# SRV-1_Expansion_Board.net
KiCad netlist of a schematic drawn in EAGLE
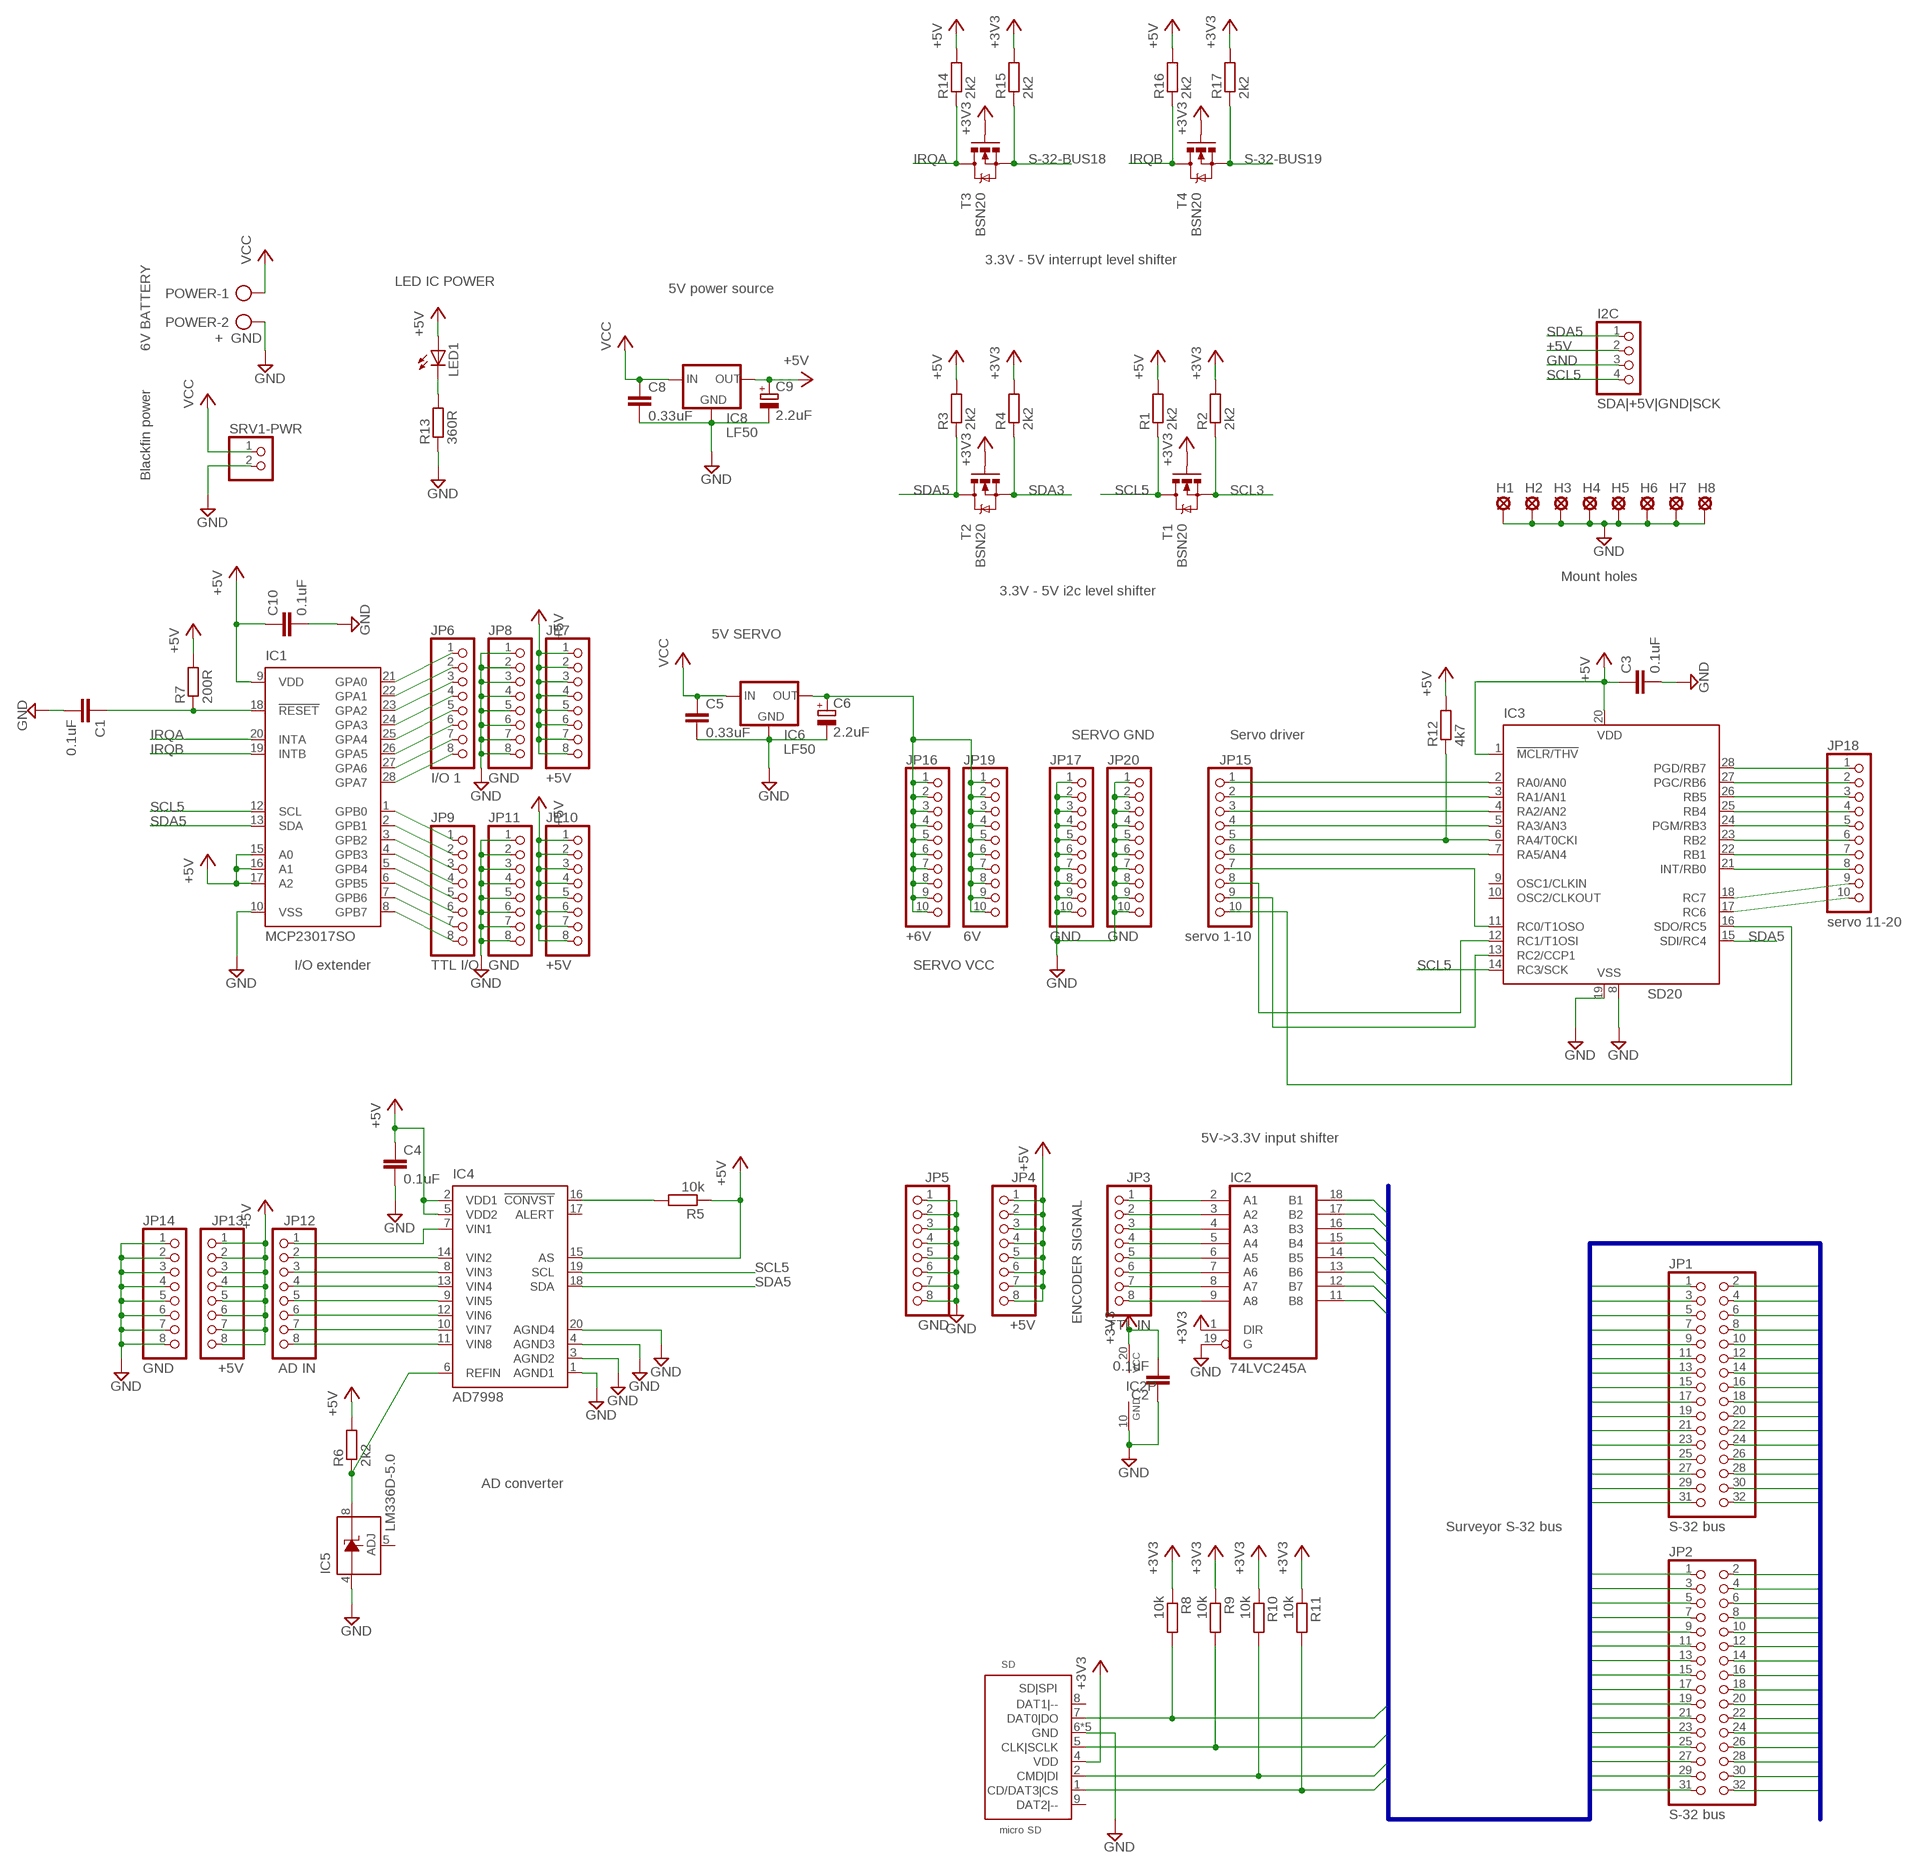
[diagram p0: schematic, sheet 1]

(export (version "E")
  (design (tool "Eeschema 10.0.6"))
  (components
    (comp (ref "C1")
      (value "0.1uF")
      (footprint "eagle-import:0805BIG")
      (libsource (lib "eagle-import") (part "CAPACITORC-0805BIG"))
    )
    (comp (ref "C2")
      (value "0.1uF")
      (footprint "eagle-import:0805BIG")
      (libsource (lib "eagle-import") (part "CAPACITORC-0805BIG"))
    )
    (comp (ref "C3")
      (value "0.1uF")
      (footprint "eagle-import:0805BIG")
      (libsource (lib "eagle-import") (part "CAPACITORC-0805BIG"))
    )
    (comp (ref "C4")
      (value "0.1uF")
      (footprint "eagle-import:0805BIG")
      (libsource (lib "eagle-import") (part "CAPACITORC-0805BIG"))
    )
    (comp (ref "C5")
      (value "0.33uF")
      (footprint "eagle-import:0805BIG")
      (libsource (lib "eagle-import") (part "CAPACITORC-0805BIG"))
    )
    (comp (ref "C6")
      (value "2.2uF")
      (footprint "eagle-import:E1,8-4")
      (libsource (lib "eagle-import") (part "CPOL-EUE1.8-4"))
    )
    (comp (ref "C8")
      (value "0.33uF")
      (footprint "eagle-import:0805BIG")
      (libsource (lib "eagle-import") (part "CAPACITORC-0805BIG"))
    )
    (comp (ref "C9")
      (value "2.2uF")
      (footprint "eagle-import:E1,8-4")
      (libsource (lib "eagle-import") (part "CPOL-EUE1.8-4"))
    )
    (comp (ref "C10")
      (value "0.1uF")
      (footprint "eagle-import:0805BIG")
      (libsource (lib "eagle-import") (part "CAPACITORC-0805BIG"))
    )
    (comp (ref "H1")
      (value "LSP35")
      (footprint "eagle-import:LSP35")
      (libsource (lib "eagle-import") (part "LSP35"))
    )
    (comp (ref "H2")
      (value "LSP35")
      (footprint "eagle-import:LSP35")
      (libsource (lib "eagle-import") (part "LSP35"))
    )
    (comp (ref "H3")
      (value "LSP35")
      (footprint "eagle-import:LSP35")
      (libsource (lib "eagle-import") (part "LSP35"))
    )
    (comp (ref "H4")
      (value "LSP35")
      (footprint "eagle-import:LSP35")
      (libsource (lib "eagle-import") (part "LSP35"))
    )
    (comp (ref "H5")
      (value "LSP40")
      (footprint "eagle-import:LSP40")
      (libsource (lib "eagle-import") (part "LSP40"))
    )
    (comp (ref "H6")
      (value "LSP40")
      (footprint "eagle-import:LSP40")
      (libsource (lib "eagle-import") (part "LSP40"))
    )
    (comp (ref "H7")
      (value "LSP40")
      (footprint "eagle-import:LSP40")
      (libsource (lib "eagle-import") (part "LSP40"))
    )
    (comp (ref "H8")
      (value "LSP40")
      (footprint "eagle-import:LSP40")
      (libsource (lib "eagle-import") (part "LSP40"))
    )
    (comp (ref "I2C")
      (value "SDA|+5V|GND|SCK")
      (footprint "eagle-import:1X04")
      (libsource (lib "eagle-import") (part "PINHD-1X4"))
    )
    (comp (ref "IC1")
      (value "MCP23017SO")
      (footprint "eagle-import:SO28W")
      (fields (field (name "MF") "MICROCHIP") (field (name "MPN") "MCP23017-E/SO"))
      (libsource (lib "eagle-import") (part "MCP23017SO"))
    )
    (comp (ref "IC2")
      (value "74LVC245A")
      (footprint "eagle-import:SO20W")
      (libsource (lib "eagle-import") (part "74245DWLS"))
    )
    (comp (ref "IC3")
      (value "SD20")
      (footprint "eagle-import:DIL28-3")
      (fields (field (name "MF") "MICROCHIP") (field (name "MPN") "PIC16F872-I/SP"))
      (libsource (lib "eagle-import") (part "PIC16872PF"))
    )
    (comp (ref "IC4")
      (value "AD7998")
      (footprint "eagle-import:TSSOP20")
      (libsource (lib "eagle-import") (part "AD7998"))
    )
    (comp (ref "IC5")
      (value "LM336D-5.0")
      (footprint "eagle-import:SO08")
      (libsource (lib "eagle-import") (part "LM336D"))
    )
    (comp (ref "IC6")
      (value "LF50")
      (footprint "eagle-import:DPAK")
      (libsource (lib "eagle-import") (part "78XXCDT"))
    )
    (comp (ref "IC8")
      (value "LF50")
      (footprint "eagle-import:DPAK")
      (libsource (lib "eagle-import") (part "78XXCDT"))
    )
    (comp (ref "JP1")
      (value "S-32 bus")
      (footprint "eagle-import:2X16")
      (libsource (lib "eagle-import") (part "PINHD-2X16"))
    )
    (comp (ref "JP2")
      (value "S-32 bus")
      (footprint "eagle-import:2X16")
      (libsource (lib "eagle-import") (part "PINHD-2X16"))
    )
    (comp (ref "JP3")
      (value "TTL IN")
      (footprint "eagle-import:1X08")
      (libsource (lib "eagle-import") (part "PINHD-1X8"))
    )
    (comp (ref "JP4")
      (value "+5V")
      (footprint "eagle-import:1X08")
      (libsource (lib "eagle-import") (part "PINHD-1X8"))
    )
    (comp (ref "JP5")
      (value "GND")
      (footprint "eagle-import:1X08")
      (libsource (lib "eagle-import") (part "PINHD-1X8"))
    )
    (comp (ref "JP6")
      (value "I/O 1")
      (footprint "eagle-import:1X08")
      (libsource (lib "eagle-import") (part "PINHD-1X8"))
    )
    (comp (ref "JP7")
      (value "+5V")
      (footprint "eagle-import:1X08")
      (libsource (lib "eagle-import") (part "PINHD-1X8"))
    )
    (comp (ref "JP8")
      (value "GND")
      (footprint "eagle-import:1X08")
      (libsource (lib "eagle-import") (part "PINHD-1X8"))
    )
    (comp (ref "JP9")
      (value "TTL I/O")
      (footprint "eagle-import:1X08")
      (libsource (lib "eagle-import") (part "PINHD-1X8"))
    )
    (comp (ref "JP10")
      (value "+5V")
      (footprint "eagle-import:1X08")
      (libsource (lib "eagle-import") (part "PINHD-1X8"))
    )
    (comp (ref "JP11")
      (value "GND")
      (footprint "eagle-import:1X08")
      (libsource (lib "eagle-import") (part "PINHD-1X8"))
    )
    (comp (ref "JP12")
      (value "AD IN")
      (footprint "eagle-import:1X08")
      (libsource (lib "eagle-import") (part "PINHD-1X8"))
    )
    (comp (ref "JP13")
      (value "+5V")
      (footprint "eagle-import:1X08")
      (libsource (lib "eagle-import") (part "PINHD-1X8"))
    )
    (comp (ref "JP14")
      (value "GND")
      (footprint "eagle-import:1X08")
      (libsource (lib "eagle-import") (part "PINHD-1X8"))
    )
    (comp (ref "JP15")
      (value "servo 1-10")
      (footprint "eagle-import:1X10")
      (libsource (lib "eagle-import") (part "PINHD-1X10"))
    )
    (comp (ref "JP16")
      (value "+6V")
      (footprint "eagle-import:1X10")
      (libsource (lib "eagle-import") (part "PINHD-1X10"))
    )
    (comp (ref "JP17")
      (value "GND")
      (footprint "eagle-import:1X10")
      (libsource (lib "eagle-import") (part "PINHD-1X10"))
    )
    (comp (ref "JP18")
      (value "servo 11-20")
      (footprint "eagle-import:1X10")
      (libsource (lib "eagle-import") (part "PINHD-1X10"))
    )
    (comp (ref "JP19")
      (value "6V")
      (footprint "eagle-import:1X10")
      (libsource (lib "eagle-import") (part "PINHD-1X10"))
    )
    (comp (ref "JP20")
      (value "GND")
      (footprint "eagle-import:1X10")
      (libsource (lib "eagle-import") (part "PINHD-1X10"))
    )
    (comp (ref "LED1")
      (value "LEDCHIPLED_1206")
      (footprint "eagle-import:CHIPLED_1206")
      (libsource (lib "eagle-import") (part "LEDCHIPLED_1206"))
    )
    (comp (ref "POWER")
      (value "+ GND")
      (footprint "eagle-import:AK500_2")
      (libsource (lib "eagle-import") (part "AK500/2"))
    )
    (comp (ref "R1")
      (value "2k2")
      (footprint "eagle-import:0805BIG")
      (libsource (lib "eagle-import") (part "RESISTORR-0805BIG"))
    )
    (comp (ref "R2")
      (value "2k2")
      (footprint "eagle-import:0805BIG")
      (libsource (lib "eagle-import") (part "RESISTORR-0805BIG"))
    )
    (comp (ref "R3")
      (value "2k2")
      (footprint "eagle-import:0805BIG")
      (libsource (lib "eagle-import") (part "RESISTORR-0805BIG"))
    )
    (comp (ref "R4")
      (value "2k2")
      (footprint "eagle-import:0805BIG")
      (libsource (lib "eagle-import") (part "RESISTORR-0805BIG"))
    )
    (comp (ref "R5")
      (value "10k")
      (footprint "eagle-import:0805BIG")
      (libsource (lib "eagle-import") (part "RESISTORR-0805BIG"))
    )
    (comp (ref "R6")
      (value "2k2")
      (footprint "eagle-import:0805BIG")
      (libsource (lib "eagle-import") (part "RESISTORR-0805BIG"))
    )
    (comp (ref "R7")
      (value "200R")
      (footprint "eagle-import:0805BIG")
      (libsource (lib "eagle-import") (part "RESISTORR-0805BIG"))
    )
    (comp (ref "R8")
      (value "10k")
      (footprint "eagle-import:0805BIG")
      (libsource (lib "eagle-import") (part "RESISTORR-0805BIG"))
    )
    (comp (ref "R9")
      (value "10k")
      (footprint "eagle-import:0805BIG")
      (libsource (lib "eagle-import") (part "RESISTORR-0805BIG"))
    )
    (comp (ref "R10")
      (value "10k")
      (footprint "eagle-import:0805BIG")
      (libsource (lib "eagle-import") (part "RESISTORR-0805BIG"))
    )
    (comp (ref "R11")
      (value "10k")
      (footprint "eagle-import:0805BIG")
      (libsource (lib "eagle-import") (part "RESISTORR-0805BIG"))
    )
    (comp (ref "R12")
      (value "4k7")
      (footprint "eagle-import:0805BIG")
      (libsource (lib "eagle-import") (part "RESISTORR-0805BIG"))
    )
    (comp (ref "R13")
      (value "360R")
      (footprint "eagle-import:0805BIG")
      (libsource (lib "eagle-import") (part "RESISTORR-0805BIG"))
    )
    (comp (ref "R14")
      (value "2k2")
      (footprint "eagle-import:0805BIG")
      (libsource (lib "eagle-import") (part "RESISTORR-0805BIG"))
    )
    (comp (ref "R15")
      (value "2k2")
      (footprint "eagle-import:0805BIG")
      (libsource (lib "eagle-import") (part "RESISTORR-0805BIG"))
    )
    (comp (ref "R16")
      (value "2k2")
      (footprint "eagle-import:0805BIG")
      (libsource (lib "eagle-import") (part "RESISTORR-0805BIG"))
    )
    (comp (ref "R17")
      (value "2k2")
      (footprint "eagle-import:0805BIG")
      (libsource (lib "eagle-import") (part "RESISTORR-0805BIG"))
    )
    (comp (ref "SD")
      (value "micro SD")
      (footprint "eagle-import:SD-500901-0801")
      (libsource (lib "eagle-import") (part "MICRO-SD_CARD_SOCKET"))
    )
    (comp (ref "SRV1-PWR")
      (value "PINHD-1X2")
      (footprint "eagle-import:1X02")
      (libsource (lib "eagle-import") (part "PINHD-1X2"))
    )
    (comp (ref "T1")
      (value "BSN20")
      (footprint "eagle-import:SOT23")
      (libsource (lib "eagle-import") (part "BSN20"))
    )
    (comp (ref "T2")
      (value "BSN20")
      (footprint "eagle-import:SOT23")
      (libsource (lib "eagle-import") (part "BSN20"))
    )
    (comp (ref "T3")
      (value "BSN20")
      (footprint "eagle-import:SOT23")
      (libsource (lib "eagle-import") (part "BSN20"))
    )
    (comp (ref "T4")
      (value "BSN20")
      (footprint "eagle-import:SOT23")
      (libsource (lib "eagle-import") (part "BSN20"))
    )
  )
  (nets
    (net (code "1") (name "+3V3") (class "Default")
      (node (ref "C2") (pin "2") (pinfunction "2_2") (pintype "passive"))
      (node (ref "IC2") (pin "1") (pinfunction "DIR_1") (pintype "input"))
      (node (ref "IC2") (pin "20") (pinfunction "VCC_20") (pintype "power_in"))
      (node (ref "JP1") (pin "1") (pinfunction "1_1") (pintype "passive"))
      (node (ref "JP2") (pin "1") (pinfunction "1_1") (pintype "passive"))
      (node (ref "R10") (pin "1") (pinfunction "1_1") (pintype "passive"))
      (node (ref "R11") (pin "1") (pinfunction "1_1") (pintype "passive"))
      (node (ref "R15") (pin "2") (pinfunction "2_2") (pintype "passive"))
      (node (ref "R17") (pin "2") (pinfunction "2_2") (pintype "passive"))
      (node (ref "R2") (pin "2") (pinfunction "2_2") (pintype "passive"))
      (node (ref "R4") (pin "2") (pinfunction "2_2") (pintype "passive"))
      (node (ref "R8") (pin "1") (pinfunction "1_1") (pintype "passive"))
      (node (ref "R9") (pin "1") (pinfunction "1_1") (pintype "passive"))
      (node (ref "SD") (pin "4") (pinfunction "VDD_4") (pintype "power_in"))
      (node (ref "T1") (pin "1") (pinfunction "G_1") (pintype "passive"))
      (node (ref "T2") (pin "1") (pinfunction "G_1") (pintype "passive"))
      (node (ref "T3") (pin "1") (pinfunction "G_1") (pintype "passive"))
      (node (ref "T4") (pin "1") (pinfunction "G_1") (pintype "passive"))
    )
    (net (code "2") (name "+5V") (class "Default")
      (node (ref "C10") (pin "1") (pinfunction "1_1") (pintype "passive"))
      (node (ref "C3") (pin "1") (pinfunction "1_1") (pintype "passive"))
      (node (ref "C4") (pin "1") (pinfunction "1_1") (pintype "passive"))
      (node (ref "C9") (pin "+") (pinfunction "+_+") (pintype "passive"))
      (node (ref "I2C") (pin "2") (pinfunction "2_2") (pintype "passive"))
      (node (ref "IC1") (pin "15") (pinfunction "A0_15") (pintype "input"))
      (node (ref "IC1") (pin "16") (pinfunction "A1_16") (pintype "input"))
      (node (ref "IC1") (pin "17") (pinfunction "A2_17") (pintype "input"))
      (node (ref "IC1") (pin "9") (pinfunction "VDD_9") (pintype "power_in"))
      (node (ref "IC3") (pin "1") (pinfunction "~{MCLR/THV}_1") (pintype "input"))
      (node (ref "IC3") (pin "20") (pinfunction "VDD_20") (pintype "power_in"))
      (node (ref "IC4") (pin "15") (pinfunction "AS_15") (pintype "input"))
      (node (ref "IC4") (pin "2") (pinfunction "VDD1_2") (pintype "power_in"))
      (node (ref "IC4") (pin "5") (pinfunction "VDD2_5") (pintype "power_in"))
      (node (ref "IC8") (pin "3") (pinfunction "OUT_3") (pintype "passive"))
      (node (ref "JP10") (pin "1") (pinfunction "1_1") (pintype "passive"))
      (node (ref "JP10") (pin "2") (pinfunction "2_2") (pintype "passive"))
      (node (ref "JP10") (pin "3") (pinfunction "3_3") (pintype "passive"))
      (node (ref "JP10") (pin "4") (pinfunction "4_4") (pintype "passive"))
      (node (ref "JP10") (pin "5") (pinfunction "5_5") (pintype "passive"))
      (node (ref "JP10") (pin "6") (pinfunction "6_6") (pintype "passive"))
      (node (ref "JP10") (pin "7") (pinfunction "7_7") (pintype "passive"))
      (node (ref "JP10") (pin "8") (pinfunction "8_8") (pintype "passive"))
      (node (ref "JP13") (pin "1") (pinfunction "1_1") (pintype "passive"))
      (node (ref "JP13") (pin "2") (pinfunction "2_2") (pintype "passive"))
      (node (ref "JP13") (pin "3") (pinfunction "3_3") (pintype "passive"))
      (node (ref "JP13") (pin "4") (pinfunction "4_4") (pintype "passive"))
      (node (ref "JP13") (pin "5") (pinfunction "5_5") (pintype "passive"))
      (node (ref "JP13") (pin "6") (pinfunction "6_6") (pintype "passive"))
      (node (ref "JP13") (pin "7") (pinfunction "7_7") (pintype "passive"))
      (node (ref "JP13") (pin "8") (pinfunction "8_8") (pintype "passive"))
      (node (ref "JP4") (pin "1") (pinfunction "1_1") (pintype "passive"))
      (node (ref "JP4") (pin "2") (pinfunction "2_2") (pintype "passive"))
      (node (ref "JP4") (pin "3") (pinfunction "3_3") (pintype "passive"))
      (node (ref "JP4") (pin "4") (pinfunction "4_4") (pintype "passive"))
      (node (ref "JP4") (pin "5") (pinfunction "5_5") (pintype "passive"))
      (node (ref "JP4") (pin "6") (pinfunction "6_6") (pintype "passive"))
      (node (ref "JP4") (pin "7") (pinfunction "7_7") (pintype "passive"))
      (node (ref "JP4") (pin "8") (pinfunction "8_8") (pintype "passive"))
      (node (ref "JP7") (pin "1") (pinfunction "1_1") (pintype "passive"))
      (node (ref "JP7") (pin "2") (pinfunction "2_2") (pintype "passive"))
      (node (ref "JP7") (pin "3") (pinfunction "3_3") (pintype "passive"))
      (node (ref "JP7") (pin "4") (pinfunction "4_4") (pintype "passive"))
      (node (ref "JP7") (pin "5") (pinfunction "5_5") (pintype "passive"))
      (node (ref "JP7") (pin "6") (pinfunction "6_6") (pintype "passive"))
      (node (ref "JP7") (pin "7") (pinfunction "7_7") (pintype "passive"))
      (node (ref "JP7") (pin "8") (pinfunction "8_8") (pintype "passive"))
      (node (ref "LED1") (pin "A") (pinfunction "A_A") (pintype "passive"))
      (node (ref "R1") (pin "2") (pinfunction "2_2") (pintype "passive"))
      (node (ref "R12") (pin "2") (pinfunction "2_2") (pintype "passive"))
      (node (ref "R14") (pin "2") (pinfunction "2_2") (pintype "passive"))
      (node (ref "R16") (pin "2") (pinfunction "2_2") (pintype "passive"))
      (node (ref "R3") (pin "2") (pinfunction "2_2") (pintype "passive"))
      (node (ref "R5") (pin "1") (pinfunction "1_1") (pintype "passive"))
      (node (ref "R6") (pin "2") (pinfunction "2_2") (pintype "passive"))
      (node (ref "R7") (pin "2") (pinfunction "2_2") (pintype "passive"))
    )
    (net (code "3") (name "/IRQA") (class "Default")
      (node (ref "IC1") (pin "20") (pinfunction "INTA_20") (pintype "output"))
      (node (ref "R14") (pin "1") (pinfunction "1_1") (pintype "passive"))
      (node (ref "T3") (pin "3") (pinfunction "D_3") (pintype "passive"))
    )
    (net (code "4") (name "/IRQB") (class "Default")
      (node (ref "IC1") (pin "19") (pinfunction "INTB_19") (pintype "output"))
      (node (ref "R16") (pin "1") (pinfunction "1_1") (pintype "passive"))
      (node (ref "T4") (pin "3") (pinfunction "D_3") (pintype "passive"))
    )
    (net (code "5") (name "/S-32-BUS3") (class "Default")
      (node (ref "JP1") (pin "3") (pinfunction "3_3") (pintype "passive"))
      (node (ref "JP2") (pin "3") (pinfunction "3_3") (pintype "passive"))
    )
    (net (code "6") (name "/S-32-BUS4") (class "Default")
      (node (ref "JP1") (pin "4") (pinfunction "4_4") (pintype "passive"))
      (node (ref "JP2") (pin "4") (pinfunction "4_4") (pintype "passive"))
    )
    (net (code "7") (name "/S-32-BUS5") (class "Default")
      (node (ref "JP1") (pin "5") (pinfunction "5_5") (pintype "passive"))
      (node (ref "JP2") (pin "5") (pinfunction "5_5") (pintype "passive"))
    )
    (net (code "8") (name "/S-32-BUS6") (class "Default")
      (node (ref "JP1") (pin "6") (pinfunction "6_6") (pintype "passive"))
      (node (ref "JP2") (pin "6") (pinfunction "6_6") (pintype "passive"))
    )
    (net (code "9") (name "/S-32-BUS7") (class "Default")
      (node (ref "JP1") (pin "7") (pinfunction "7_7") (pintype "passive"))
      (node (ref "JP2") (pin "7") (pinfunction "7_7") (pintype "passive"))
    )
    (net (code "10") (name "/S-32-BUS8") (class "Default")
      (node (ref "JP1") (pin "8") (pinfunction "8_8") (pintype "passive"))
      (node (ref "JP2") (pin "8") (pinfunction "8_8") (pintype "passive"))
    )
    (net (code "11") (name "/S-32-BUS9") (class "Default")
      (node (ref "JP1") (pin "9") (pinfunction "9_9") (pintype "passive"))
      (node (ref "JP2") (pin "9") (pinfunction "9_9") (pintype "passive"))
      (node (ref "R10") (pin "2") (pinfunction "2_2") (pintype "passive"))
      (node (ref "SD") (pin "2") (pinfunction "CMD|DI_2") (pintype "bidirectional"))
    )
    (net (code "12") (name "/S-32-BUS10") (class "Default")
      (node (ref "JP1") (pin "10") (pinfunction "10_10") (pintype "passive"))
      (node (ref "JP2") (pin "10") (pinfunction "10_10") (pintype "passive"))
      (node (ref "R8") (pin "2") (pinfunction "2_2") (pintype "passive"))
      (node (ref "SD") (pin "7") (pinfunction "DAT0|DO_7") (pintype "bidirectional"))
    )
    (net (code "13") (name "/S-32-BUS11") (class "Default")
      (node (ref "JP1") (pin "11") (pinfunction "11_11") (pintype "passive"))
      (node (ref "JP2") (pin "11") (pinfunction "11_11") (pintype "passive"))
      (node (ref "R9") (pin "2") (pinfunction "2_2") (pintype "passive"))
      (node (ref "SD") (pin "5") (pinfunction "CLK|SCLK_5") (pintype "bidirectional"))
    )
    (net (code "14") (name "/S-32-BUS12") (class "Default")
      (node (ref "JP1") (pin "12") (pinfunction "12_12") (pintype "passive"))
      (node (ref "JP2") (pin "12") (pinfunction "12_12") (pintype "passive"))
      (node (ref "R11") (pin "2") (pinfunction "2_2") (pintype "passive"))
      (node (ref "SD") (pin "1") (pinfunction "CD/DAT3|CS_1") (pintype "bidirectional"))
    )
    (net (code "15") (name "/S-32-BUS13") (class "Default")
      (node (ref "JP1") (pin "13") (pinfunction "13_13") (pintype "passive"))
      (node (ref "JP2") (pin "13") (pinfunction "13_13") (pintype "passive"))
    )
    (net (code "16") (name "/S-32-BUS17") (class "Default")
      (node (ref "JP1") (pin "17") (pinfunction "17_17") (pintype "passive"))
      (node (ref "JP2") (pin "17") (pinfunction "17_17") (pintype "passive"))
    )
    (net (code "17") (name "/S-32-BUS18") (class "Default")
      (node (ref "JP1") (pin "18") (pinfunction "18_18") (pintype "passive"))
      (node (ref "JP2") (pin "18") (pinfunction "18_18") (pintype "passive"))
      (node (ref "R15") (pin "1") (pinfunction "1_1") (pintype "passive"))
      (node (ref "T3") (pin "2") (pinfunction "S_2") (pintype "passive"))
    )
    (net (code "18") (name "/S-32-BUS19") (class "Default")
      (node (ref "JP1") (pin "19") (pinfunction "19_19") (pintype "passive"))
      (node (ref "JP2") (pin "19") (pinfunction "19_19") (pintype "passive"))
      (node (ref "R17") (pin "1") (pinfunction "1_1") (pintype "passive"))
      (node (ref "T4") (pin "2") (pinfunction "S_2") (pintype "passive"))
    )
    (net (code "19") (name "/S-32-BUS20") (class "Default")
      (node (ref "JP1") (pin "20") (pinfunction "20_20") (pintype "passive"))
      (node (ref "JP2") (pin "20") (pinfunction "20_20") (pintype "passive"))
    )
    (net (code "20") (name "/S-32-BUS21") (class "Default")
      (node (ref "JP1") (pin "21") (pinfunction "21_21") (pintype "passive"))
      (node (ref "JP2") (pin "21") (pinfunction "21_21") (pintype "passive"))
    )
    (net (code "21") (name "/S-32-BUS22") (class "Default")
      (node (ref "JP1") (pin "22") (pinfunction "22_22") (pintype "passive"))
      (node (ref "JP2") (pin "22") (pinfunction "22_22") (pintype "passive"))
    )
    (net (code "22") (name "/S-32-BUS23") (class "Default")
      (node (ref "JP1") (pin "23") (pinfunction "23_23") (pintype "passive"))
      (node (ref "JP2") (pin "23") (pinfunction "23_23") (pintype "passive"))
    )
    (net (code "23") (name "/S-32-BUS24") (class "Default")
      (node (ref "JP1") (pin "24") (pinfunction "24_24") (pintype "passive"))
      (node (ref "JP2") (pin "24") (pinfunction "24_24") (pintype "passive"))
    )
    (net (code "24") (name "/S-32-BUS25") (class "Default")
      (node (ref "IC2") (pin "18") (pinfunction "B1_18") (pintype "bidirectional"))
      (node (ref "JP1") (pin "25") (pinfunction "25_25") (pintype "passive"))
      (node (ref "JP2") (pin "25") (pinfunction "25_25") (pintype "passive"))
    )
    (net (code "25") (name "/S-32-BUS26") (class "Default")
      (node (ref "IC2") (pin "17") (pinfunction "B2_17") (pintype "bidirectional"))
      (node (ref "JP1") (pin "26") (pinfunction "26_26") (pintype "passive"))
      (node (ref "JP2") (pin "26") (pinfunction "26_26") (pintype "passive"))
    )
    (net (code "26") (name "/S-32-BUS27") (class "Default")
      (node (ref "IC2") (pin "16") (pinfunction "B3_16") (pintype "bidirectional"))
      (node (ref "JP1") (pin "27") (pinfunction "27_27") (pintype "passive"))
      (node (ref "JP2") (pin "27") (pinfunction "27_27") (pintype "passive"))
    )
    (net (code "27") (name "/S-32-BUS28") (class "Default")
      (node (ref "IC2") (pin "15") (pinfunction "B4_15") (pintype "bidirectional"))
      (node (ref "JP1") (pin "28") (pinfunction "28_28") (pintype "passive"))
      (node (ref "JP2") (pin "28") (pinfunction "28_28") (pintype "passive"))
    )
    (net (code "28") (name "/S-32-BUS29") (class "Default")
      (node (ref "IC2") (pin "14") (pinfunction "B5_14") (pintype "bidirectional"))
      (node (ref "JP1") (pin "29") (pinfunction "29_29") (pintype "passive"))
      (node (ref "JP2") (pin "29") (pinfunction "29_29") (pintype "passive"))
    )
    (net (code "29") (name "/S-32-BUS30") (class "Default")
      (node (ref "IC2") (pin "13") (pinfunction "B6_13") (pintype "bidirectional"))
      (node (ref "JP1") (pin "30") (pinfunction "30_30") (pintype "passive"))
      (node (ref "JP2") (pin "30") (pinfunction "30_30") (pintype "passive"))
    )
    (net (code "30") (name "/S-32-BUS31") (class "Default")
      (node (ref "IC2") (pin "12") (pinfunction "B7_12") (pintype "bidirectional"))
      (node (ref "JP1") (pin "31") (pinfunction "31_31") (pintype "passive"))
      (node (ref "JP2") (pin "31") (pinfunction "31_31") (pintype "passive"))
    )
    (net (code "31") (name "/S-32-BUS32") (class "Default")
      (node (ref "IC2") (pin "11") (pinfunction "B8_11") (pintype "bidirectional"))
      (node (ref "JP1") (pin "32") (pinfunction "32_32") (pintype "passive"))
      (node (ref "JP2") (pin "32") (pinfunction "32_32") (pintype "passive"))
    )
    (net (code "32") (name "/SCL3") (class "Default")
      (node (ref "JP1") (pin "14") (pinfunction "14_14") (pintype "passive"))
      (node (ref "JP2") (pin "14") (pinfunction "14_14") (pintype "passive"))
      (node (ref "R2") (pin "1") (pinfunction "1_1") (pintype "passive"))
      (node (ref "T1") (pin "2") (pinfunction "S_2") (pintype "passive"))
    )
    (net (code "33") (name "/SCL5") (class "Default")
      (node (ref "I2C") (pin "4") (pinfunction "4_4") (pintype "passive"))
      (node (ref "IC1") (pin "12") (pinfunction "SCL_12") (pintype "input"))
      (node (ref "IC3") (pin "14") (pinfunction "RC3/SCK_14") (pintype "bidirectional"))
      (node (ref "IC4") (pin "19") (pinfunction "SCL_19") (pintype "input"))
      (node (ref "R1") (pin "1") (pinfunction "1_1") (pintype "passive"))
      (node (ref "T1") (pin "3") (pinfunction "D_3") (pintype "passive"))
    )
    (net (code "34") (name "/SDA3") (class "Default")
      (node (ref "JP1") (pin "15") (pinfunction "15_15") (pintype "passive"))
      (node (ref "JP2") (pin "15") (pinfunction "15_15") (pintype "passive"))
      (node (ref "R4") (pin "1") (pinfunction "1_1") (pintype "passive"))
      (node (ref "T2") (pin "2") (pinfunction "S_2") (pintype "passive"))
    )
    (net (code "35") (name "/SDA5") (class "Default")
      (node (ref "I2C") (pin "1") (pinfunction "1_1") (pintype "passive"))
      (node (ref "IC1") (pin "13") (pinfunction "SDA_13") (pintype "bidirectional"))
      (node (ref "IC3") (pin "15") (pinfunction "SDI/RC4_15") (pintype "bidirectional"))
      (node (ref "IC4") (pin "18") (pinfunction "SDA_18") (pintype "bidirectional"))
      (node (ref "R3") (pin "1") (pinfunction "1_1") (pintype "passive"))
      (node (ref "T2") (pin "3") (pinfunction "D_3") (pintype "passive"))
    )
    (net (code "36") (name "GND") (class "Default")
      (node (ref "C1") (pin "2") (pinfunction "2_2") (pintype "passive"))
      (node (ref "C10") (pin "2") (pinfunction "2_2") (pintype "passive"))
      (node (ref "C2") (pin "1") (pinfunction "1_1") (pintype "passive"))
      (node (ref "C3") (pin "2") (pinfunction "2_2") (pintype "passive"))
      (node (ref "C4") (pin "2") (pinfunction "2_2") (pintype "passive"))
      (node (ref "C5") (pin "2") (pinfunction "2_2") (pintype "passive"))
      (node (ref "C6") (pin "-") (pinfunction "-_-") (pintype "passive"))
      (node (ref "C8") (pin "2") (pinfunction "2_2") (pintype "passive"))
      (node (ref "C9") (pin "-") (pinfunction "-_-") (pintype "passive"))
      (node (ref "H1") (pin "MP") (pinfunction "MP_MP") (pintype "passive"))
      (node (ref "H2") (pin "MP") (pinfunction "MP_MP") (pintype "passive"))
      (node (ref "H3") (pin "MP") (pinfunction "MP_MP") (pintype "passive"))
      (node (ref "H4") (pin "MP") (pinfunction "MP_MP") (pintype "passive"))
      (node (ref "H5") (pin "MP") (pinfunction "MP_MP") (pintype "passive"))
      (node (ref "H6") (pin "MP") (pinfunction "MP_MP") (pintype "passive"))
      (node (ref "H7") (pin "MP") (pinfunction "MP_MP") (pintype "passive"))
      (node (ref "H8") (pin "MP") (pinfunction "MP_MP") (pintype "passive"))
      (node (ref "I2C") (pin "3") (pinfunction "3_3") (pintype "passive"))
      (node (ref "IC1") (pin "10") (pinfunction "VSS_10") (pintype "power_in"))
      (node (ref "IC2") (pin "10") (pinfunction "GND_10") (pintype "power_in"))
      (node (ref "IC2") (pin "19") (pinfunction "G_19") (pintype "input"))
      (node (ref "IC3") (pin "19") (pinfunction "VSS_19") (pintype "power_in"))
      (node (ref "IC3") (pin "8") (pinfunction "VSS_8") (pintype "power_in"))
      (node (ref "IC4") (pin "1") (pinfunction "AGND1_1") (pintype "power_in"))
      (node (ref "IC4") (pin "20") (pinfunction "AGND4_20") (pintype "power_in"))
      (node (ref "IC4") (pin "3") (pinfunction "AGND2_3") (pintype "power_in"))
      (node (ref "IC4") (pin "4") (pinfunction "AGND3_4") (pintype "power_in"))
      (node (ref "IC5") (pin "4") (pinfunction "A_4") (pintype "input"))
      (node (ref "IC6") (pin "2") (pinfunction "GND_2") (pintype "input"))
      (node (ref "IC8") (pin "2") (pinfunction "GND_2") (pintype "input"))
      (node (ref "JP1") (pin "16") (pinfunction "16_16") (pintype "passive"))
      (node (ref "JP1") (pin "2") (pinfunction "2_2") (pintype "passive"))
      (node (ref "JP11") (pin "1") (pinfunction "1_1") (pintype "passive"))
      (node (ref "JP11") (pin "2") (pinfunction "2_2") (pintype "passive"))
      (node (ref "JP11") (pin "3") (pinfunction "3_3") (pintype "passive"))
      (node (ref "JP11") (pin "4") (pinfunction "4_4") (pintype "passive"))
      (node (ref "JP11") (pin "5") (pinfunction "5_5") (pintype "passive"))
      (node (ref "JP11") (pin "6") (pinfunction "6_6") (pintype "passive"))
      (node (ref "JP11") (pin "7") (pinfunction "7_7") (pintype "passive"))
      (node (ref "JP11") (pin "8") (pinfunction "8_8") (pintype "passive"))
      (node (ref "JP14") (pin "1") (pinfunction "1_1") (pintype "passive"))
      (node (ref "JP14") (pin "2") (pinfunction "2_2") (pintype "passive"))
      (node (ref "JP14") (pin "3") (pinfunction "3_3") (pintype "passive"))
      (node (ref "JP14") (pin "4") (pinfunction "4_4") (pintype "passive"))
      (node (ref "JP14") (pin "5") (pinfunction "5_5") (pintype "passive"))
      (node (ref "JP14") (pin "6") (pinfunction "6_6") (pintype "passive"))
      (node (ref "JP14") (pin "7") (pinfunction "7_7") (pintype "passive"))
      (node (ref "JP14") (pin "8") (pinfunction "8_8") (pintype "passive"))
      (node (ref "JP17") (pin "1") (pinfunction "1_1") (pintype "passive"))
      (node (ref "JP17") (pin "10") (pinfunction "10_10") (pintype "passive"))
      (node (ref "JP17") (pin "2") (pinfunction "2_2") (pintype "passive"))
      (node (ref "JP17") (pin "3") (pinfunction "3_3") (pintype "passive"))
      (node (ref "JP17") (pin "4") (pinfunction "4_4") (pintype "passive"))
      (node (ref "JP17") (pin "5") (pinfunction "5_5") (pintype "passive"))
      (node (ref "JP17") (pin "6") (pinfunction "6_6") (pintype "passive"))
      (node (ref "JP17") (pin "7") (pinfunction "7_7") (pintype "passive"))
      (node (ref "JP17") (pin "8") (pinfunction "8_8") (pintype "passive"))
      (node (ref "JP17") (pin "9") (pinfunction "9_9") (pintype "passive"))
      (node (ref "JP2") (pin "16") (pinfunction "16_16") (pintype "passive"))
      (node (ref "JP2") (pin "2") (pinfunction "2_2") (pintype "passive"))
      (node (ref "JP20") (pin "1") (pinfunction "1_1") (pintype "passive"))
      (node (ref "JP20") (pin "10") (pinfunction "10_10") (pintype "passive"))
      (node (ref "JP20") (pin "2") (pinfunction "2_2") (pintype "passive"))
      (node (ref "JP20") (pin "3") (pinfunction "3_3") (pintype "passive"))
      (node (ref "JP20") (pin "4") (pinfunction "4_4") (pintype "passive"))
      (node (ref "JP20") (pin "5") (pinfunction "5_5") (pintype "passive"))
      (node (ref "JP20") (pin "6") (pinfunction "6_6") (pintype "passive"))
      (node (ref "JP20") (pin "7") (pinfunction "7_7") (pintype "passive"))
      (node (ref "JP20") (pin "8") (pinfunction "8_8") (pintype "passive"))
      (node (ref "JP20") (pin "9") (pinfunction "9_9") (pintype "passive"))
      (node (ref "JP5") (pin "1") (pinfunction "1_1") (pintype "passive"))
      (node (ref "JP5") (pin "2") (pinfunction "2_2") (pintype "passive"))
      (node (ref "JP5") (pin "3") (pinfunction "3_3") (pintype "passive"))
      (node (ref "JP5") (pin "4") (pinfunction "4_4") (pintype "passive"))
      (node (ref "JP5") (pin "5") (pinfunction "5_5") (pintype "passive"))
      (node (ref "JP5") (pin "6") (pinfunction "6_6") (pintype "passive"))
      (node (ref "JP5") (pin "7") (pinfunction "7_7") (pintype "passive"))
      (node (ref "JP5") (pin "8") (pinfunction "8_8") (pintype "passive"))
      (node (ref "JP8") (pin "1") (pinfunction "1_1") (pintype "passive"))
      (node (ref "JP8") (pin "2") (pinfunction "2_2") (pintype "passive"))
      (node (ref "JP8") (pin "3") (pinfunction "3_3") (pintype "passive"))
      (node (ref "JP8") (pin "4") (pinfunction "4_4") (pintype "passive"))
      (node (ref "JP8") (pin "5") (pinfunction "5_5") (pintype "passive"))
      (node (ref "JP8") (pin "6") (pinfunction "6_6") (pintype "passive"))
      (node (ref "JP8") (pin "7") (pinfunction "7_7") (pintype "passive"))
      (node (ref "JP8") (pin "8") (pinfunction "8_8") (pintype "passive"))
      (node (ref "POWER") (pin "2") (pinfunction "KL_2") (pintype "passive"))
      (node (ref "R13") (pin "1") (pinfunction "1_1") (pintype "passive"))
      (node (ref "SD") (pin "6") (pinfunction "GND_6") (pintype "power_in"))
      (node (ref "SD") (pin "GND1") (pinfunction "GND_GND1") (pintype "power_in"))
      (node (ref "SD") (pin "GND2") (pinfunction "GND_GND2") (pintype "power_in"))
      (node (ref "SD") (pin "GND3") (pinfunction "GND_GND3") (pintype "power_in"))
      (node (ref "SD") (pin "GND4") (pinfunction "GND_GND4") (pintype "power_in"))
      (node (ref "SRV1-PWR") (pin "2") (pinfunction "2_2") (pintype "passive"))
    )
    (net (code "37") (name "Net-(IC1-GPA0)") (class "Default")
      (node (ref "IC1") (pin "21") (pinfunction "GPA0_21") (pintype "bidirectional"))
      (node (ref "JP6") (pin "1") (pinfunction "1_1") (pintype "passive"))
    )
    (net (code "38") (name "Net-(IC1-GPA1)") (class "Default")
      (node (ref "IC1") (pin "22") (pinfunction "GPA1_22") (pintype "bidirectional"))
      (node (ref "JP6") (pin "2") (pinfunction "2_2") (pintype "passive"))
    )
    (net (code "39") (name "Net-(IC1-GPA2)") (class "Default")
      (node (ref "IC1") (pin "23") (pinfunction "GPA2_23") (pintype "bidirectional"))
      (node (ref "JP6") (pin "3") (pinfunction "3_3") (pintype "passive"))
    )
    (net (code "40") (name "Net-(IC1-GPA3)") (class "Default")
      (node (ref "IC1") (pin "24") (pinfunction "GPA3_24") (pintype "bidirectional"))
      (node (ref "JP6") (pin "4") (pinfunction "4_4") (pintype "passive"))
    )
    (net (code "41") (name "Net-(IC1-GPA4)") (class "Default")
      (node (ref "IC1") (pin "25") (pinfunction "GPA4_25") (pintype "bidirectional"))
      (node (ref "JP6") (pin "5") (pinfunction "5_5") (pintype "passive"))
    )
    (net (code "42") (name "Net-(IC1-GPA5)") (class "Default")
      (node (ref "IC1") (pin "26") (pinfunction "GPA5_26") (pintype "bidirectional"))
      (node (ref "JP6") (pin "6") (pinfunction "6_6") (pintype "passive"))
    )
    (net (code "43") (name "Net-(IC1-GPA6)") (class "Default")
      (node (ref "IC1") (pin "27") (pinfunction "GPA6_27") (pintype "bidirectional"))
      (node (ref "JP6") (pin "7") (pinfunction "7_7") (pintype "passive"))
    )
    (net (code "44") (name "Net-(IC1-GPA7)") (class "Default")
      (node (ref "IC1") (pin "28") (pinfunction "GPA7_28") (pintype "bidirectional"))
      (node (ref "JP6") (pin "8") (pinfunction "8_8") (pintype "passive"))
    )
    (net (code "45") (name "Net-(IC1-GPB0)") (class "Default")
      (node (ref "IC1") (pin "1") (pinfunction "GPB0_1") (pintype "bidirectional"))
      (node (ref "JP9") (pin "1") (pinfunction "1_1") (pintype "passive"))
    )
    (net (code "46") (name "Net-(IC1-GPB1)") (class "Default")
      (node (ref "IC1") (pin "2") (pinfunction "GPB1_2") (pintype "bidirectional"))
      (node (ref "JP9") (pin "2") (pinfunction "2_2") (pintype "passive"))
    )
    (net (code "47") (name "Net-(IC1-GPB2)") (class "Default")
      (node (ref "IC1") (pin "3") (pinfunction "GPB2_3") (pintype "bidirectional"))
      (node (ref "JP9") (pin "3") (pinfunction "3_3") (pintype "passive"))
    )
    (net (code "48") (name "Net-(IC1-GPB3)") (class "Default")
      (node (ref "IC1") (pin "4") (pinfunction "GPB3_4") (pintype "bidirectional"))
      (node (ref "JP9") (pin "4") (pinfunction "4_4") (pintype "passive"))
    )
    (net (code "49") (name "Net-(IC1-GPB4)") (class "Default")
      (node (ref "IC1") (pin "5") (pinfunction "GPB4_5") (pintype "bidirectional"))
      (node (ref "JP9") (pin "5") (pinfunction "5_5") (pintype "passive"))
    )
    (net (code "50") (name "Net-(IC1-GPB5)") (class "Default")
      (node (ref "IC1") (pin "6") (pinfunction "GPB5_6") (pintype "bidirectional"))
      (node (ref "JP9") (pin "6") (pinfunction "6_6") (pintype "passive"))
    )
    (net (code "51") (name "Net-(IC1-GPB6)") (class "Default")
      (node (ref "IC1") (pin "7") (pinfunction "GPB6_7") (pintype "bidirectional"))
      (node (ref "JP9") (pin "7") (pinfunction "7_7") (pintype "passive"))
    )
    (net (code "52") (name "Net-(IC1-GPB7)") (class "Default")
      (node (ref "IC1") (pin "8") (pinfunction "GPB7_8") (pintype "bidirectional"))
      (node (ref "JP9") (pin "8") (pinfunction "8_8") (pintype "passive"))
    )
    (net (code "53") (name "Net-(IC1-~{RESET})") (class "Default")
      (node (ref "C1") (pin "1") (pinfunction "1_1") (pintype "passive"))
      (node (ref "IC1") (pin "18") (pinfunction "~{RESET}_18") (pintype "input"))
      (node (ref "R7") (pin "1") (pinfunction "1_1") (pintype "passive"))
    )
    (net (code "54") (name "Net-(IC2A-A1)") (class "Default")
      (node (ref "IC2") (pin "2") (pinfunction "A1_2") (pintype "bidirectional"))
      (node (ref "JP3") (pin "1") (pinfunction "1_1") (pintype "passive"))
    )
    (net (code "55") (name "Net-(IC2A-A2)") (class "Default")
      (node (ref "IC2") (pin "3") (pinfunction "A2_3") (pintype "bidirectional"))
      (node (ref "JP3") (pin "2") (pinfunction "2_2") (pintype "passive"))
    )
    (net (code "56") (name "Net-(IC2A-A3)") (class "Default")
      (node (ref "IC2") (pin "4") (pinfunction "A3_4") (pintype "bidirectional"))
      (node (ref "JP3") (pin "3") (pinfunction "3_3") (pintype "passive"))
    )
    (net (code "57") (name "Net-(IC2A-A4)") (class "Default")
      (node (ref "IC2") (pin "5") (pinfunction "A4_5") (pintype "bidirectional"))
      (node (ref "JP3") (pin "4") (pinfunction "4_4") (pintype "passive"))
    )
    (net (code "58") (name "Net-(IC2A-A5)") (class "Default")
      (node (ref "IC2") (pin "6") (pinfunction "A5_6") (pintype "bidirectional"))
      (node (ref "JP3") (pin "5") (pinfunction "5_5") (pintype "passive"))
    )
    (net (code "59") (name "Net-(IC2A-A6)") (class "Default")
      (node (ref "IC2") (pin "7") (pinfunction "A6_7") (pintype "bidirectional"))
      (node (ref "JP3") (pin "6") (pinfunction "6_6") (pintype "passive"))
    )
    (net (code "60") (name "Net-(IC2A-A7)") (class "Default")
      (node (ref "IC2") (pin "8") (pinfunction "A7_8") (pintype "bidirectional"))
      (node (ref "JP3") (pin "7") (pinfunction "7_7") (pintype "passive"))
    )
    (net (code "61") (name "Net-(IC2A-A8)") (class "Default")
      (node (ref "IC2") (pin "9") (pinfunction "A8_9") (pintype "bidirectional"))
      (node (ref "JP3") (pin "8") (pinfunction "8_8") (pintype "passive"))
    )
    (net (code "62") (name "Net-(IC3-INT{slash}RB0)") (class "Default")
      (node (ref "IC3") (pin "21") (pinfunction "INT/RB0_21") (pintype "bidirectional"))
      (node (ref "JP18") (pin "8") (pinfunction "8_8") (pintype "passive"))
    )
    (net (code "63") (name "Net-(IC3-PGC{slash}RB6)") (class "Default")
      (node (ref "IC3") (pin "27") (pinfunction "PGC/RB6_27") (pintype "bidirectional"))
      (node (ref "JP18") (pin "2") (pinfunction "2_2") (pintype "passive"))
    )
    (net (code "64") (name "Net-(IC3-PGD{slash}RB7)") (class "Default")
      (node (ref "IC3") (pin "28") (pinfunction "PGD/RB7_28") (pintype "bidirectional"))
      (node (ref "JP18") (pin "1") (pinfunction "1_1") (pintype "passive"))
    )
    (net (code "65") (name "Net-(IC3-PGM{slash}RB3)") (class "Default")
      (node (ref "IC3") (pin "24") (pinfunction "PGM/RB3_24") (pintype "bidirectional"))
      (node (ref "JP18") (pin "5") (pinfunction "5_5") (pintype "passive"))
    )
    (net (code "66") (name "Net-(IC3-RA0{slash}AN0)") (class "Default")
      (node (ref "IC3") (pin "2") (pinfunction "RA0/AN0_2") (pintype "bidirectional"))
      (node (ref "JP15") (pin "1") (pinfunction "1_1") (pintype "passive"))
    )
    (net (code "67") (name "Net-(IC3-RA1{slash}AN1)") (class "Default")
      (node (ref "IC3") (pin "3") (pinfunction "RA1/AN1_3") (pintype "bidirectional"))
      (node (ref "JP15") (pin "2") (pinfunction "2_2") (pintype "passive"))
    )
    (net (code "68") (name "Net-(IC3-RA2{slash}AN2)") (class "Default")
      (node (ref "IC3") (pin "4") (pinfunction "RA2/AN2_4") (pintype "bidirectional"))
      (node (ref "JP15") (pin "3") (pinfunction "3_3") (pintype "passive"))
    )
    (net (code "69") (name "Net-(IC3-RA3{slash}AN3)") (class "Default")
      (node (ref "IC3") (pin "5") (pinfunction "RA3/AN3_5") (pintype "bidirectional"))
      (node (ref "JP15") (pin "4") (pinfunction "4_4") (pintype "passive"))
    )
    (net (code "70") (name "Net-(IC3-RA4{slash}T0CKI)") (class "Default")
      (node (ref "IC3") (pin "6") (pinfunction "RA4/T0CKI_6") (pintype "bidirectional"))
      (node (ref "JP15") (pin "5") (pinfunction "5_5") (pintype "passive"))
      (node (ref "R12") (pin "1") (pinfunction "1_1") (pintype "passive"))
    )
    (net (code "71") (name "Net-(IC3-RA5{slash}AN4)") (class "Default")
      (node (ref "IC3") (pin "7") (pinfunction "RA5/AN4_7") (pintype "bidirectional"))
      (node (ref "JP15") (pin "6") (pinfunction "6_6") (pintype "passive"))
    )
    (net (code "72") (name "Net-(IC3-RB1)") (class "Default")
      (node (ref "IC3") (pin "22") (pinfunction "RB1_22") (pintype "bidirectional"))
      (node (ref "JP18") (pin "7") (pinfunction "7_7") (pintype "passive"))
    )
    (net (code "73") (name "Net-(IC3-RB2)") (class "Default")
      (node (ref "IC3") (pin "23") (pinfunction "RB2_23") (pintype "bidirectional"))
      (node (ref "JP18") (pin "6") (pinfunction "6_6") (pintype "passive"))
    )
    (net (code "74") (name "Net-(IC3-RB4)") (class "Default")
      (node (ref "IC3") (pin "25") (pinfunction "RB4_25") (pintype "bidirectional"))
      (node (ref "JP18") (pin "4") (pinfunction "4_4") (pintype "passive"))
    )
    (net (code "75") (name "Net-(IC3-RB5)") (class "Default")
      (node (ref "IC3") (pin "26") (pinfunction "RB5_26") (pintype "bidirectional"))
      (node (ref "JP18") (pin "3") (pinfunction "3_3") (pintype "passive"))
    )
    (net (code "76") (name "Net-(IC3-RC0{slash}T1OSO)") (class "Default")
      (node (ref "IC3") (pin "11") (pinfunction "RC0/T1OSO_11") (pintype "bidirectional"))
      (node (ref "JP15") (pin "7") (pinfunction "7_7") (pintype "passive"))
    )
    (net (code "77") (name "Net-(IC3-RC1{slash}T1OSI)") (class "Default")
      (node (ref "IC3") (pin "12") (pinfunction "RC1/T1OSI_12") (pintype "bidirectional"))
      (node (ref "JP15") (pin "8") (pinfunction "8_8") (pintype "passive"))
    )
    (net (code "78") (name "Net-(IC3-RC2{slash}CCP1)") (class "Default")
      (node (ref "IC3") (pin "13") (pinfunction "RC2/CCP1_13") (pintype "bidirectional"))
      (node (ref "JP15") (pin "9") (pinfunction "9_9") (pintype "passive"))
    )
    (net (code "79") (name "Net-(IC3-RC6)") (class "Default")
      (node (ref "IC3") (pin "17") (pinfunction "RC6_17") (pintype "bidirectional"))
      (node (ref "JP18") (pin "10") (pinfunction "10_10") (pintype "passive"))
    )
    (net (code "80") (name "Net-(IC3-RC7)") (class "Default")
      (node (ref "IC3") (pin "18") (pinfunction "RC7_18") (pintype "bidirectional"))
      (node (ref "JP18") (pin "9") (pinfunction "9_9") (pintype "passive"))
    )
    (net (code "81") (name "Net-(IC3-SDO{slash}RC5)") (class "Default")
      (node (ref "IC3") (pin "16") (pinfunction "SDO/RC5_16") (pintype "bidirectional"))
      (node (ref "JP15") (pin "10") (pinfunction "10_10") (pintype "passive"))
    )
    (net (code "82") (name "Net-(IC4-REFIN)") (class "Default")
      (node (ref "IC4") (pin "6") (pinfunction "REFIN_6") (pintype "bidirectional"))
      (node (ref "IC5") (pin "8") (pinfunction "C_8") (pintype "passive"))
      (node (ref "R6") (pin "1") (pinfunction "1_1") (pintype "passive"))
    )
    (net (code "83") (name "Net-(IC4-VIN1)") (class "Default")
      (node (ref "IC4") (pin "7") (pinfunction "VIN1_7") (pintype "input"))
      (node (ref "JP12") (pin "1") (pinfunction "1_1") (pintype "passive"))
    )
    (net (code "84") (name "Net-(IC4-VIN2)") (class "Default")
      (node (ref "IC4") (pin "14") (pinfunction "VIN2_14") (pintype "input"))
      (node (ref "JP12") (pin "2") (pinfunction "2_2") (pintype "passive"))
    )
    (net (code "85") (name "Net-(IC4-VIN3)") (class "Default")
      (node (ref "IC4") (pin "8") (pinfunction "VIN3_8") (pintype "bidirectional"))
      (node (ref "JP12") (pin "3") (pinfunction "3_3") (pintype "passive"))
    )
    (net (code "86") (name "Net-(IC4-VIN4)") (class "Default")
      (node (ref "IC4") (pin "13") (pinfunction "VIN4_13") (pintype "bidirectional"))
      (node (ref "JP12") (pin "4") (pinfunction "4_4") (pintype "passive"))
    )
    (net (code "87") (name "Net-(IC4-VIN5)") (class "Default")
      (node (ref "IC4") (pin "9") (pinfunction "VIN5_9") (pintype "bidirectional"))
      (node (ref "JP12") (pin "5") (pinfunction "5_5") (pintype "passive"))
    )
    (net (code "88") (name "Net-(IC4-VIN6)") (class "Default")
      (node (ref "IC4") (pin "12") (pinfunction "VIN6_12") (pintype "bidirectional"))
      (node (ref "JP12") (pin "6") (pinfunction "6_6") (pintype "passive"))
    )
    (net (code "89") (name "Net-(IC4-VIN7)") (class "Default")
      (node (ref "IC4") (pin "10") (pinfunction "VIN7_10") (pintype "bidirectional"))
      (node (ref "JP12") (pin "7") (pinfunction "7_7") (pintype "passive"))
    )
    (net (code "90") (name "Net-(IC4-VIN8)") (class "Default")
      (node (ref "IC4") (pin "11") (pinfunction "VIN8_11") (pintype "bidirectional"))
      (node (ref "JP12") (pin "8") (pinfunction "8_8") (pintype "passive"))
    )
    (net (code "91") (name "Net-(IC4-~{CONVST})") (class "Default")
      (node (ref "IC4") (pin "16") (pinfunction "~{CONVST}_16") (pintype "input"))
      (node (ref "R5") (pin "2") (pinfunction "2_2") (pintype "passive"))
    )
    (net (code "92") (name "Net-(IC6-OUT)") (class "Default")
      (node (ref "C6") (pin "+") (pinfunction "+_+") (pintype "passive"))
      (node (ref "IC6") (pin "3") (pinfunction "OUT_3") (pintype "passive"))
      (node (ref "JP16") (pin "1") (pinfunction "1_1") (pintype "passive"))
      (node (ref "JP16") (pin "10") (pinfunction "10_10") (pintype "passive"))
      (node (ref "JP16") (pin "2") (pinfunction "2_2") (pintype "passive"))
      (node (ref "JP16") (pin "3") (pinfunction "3_3") (pintype "passive"))
      (node (ref "JP16") (pin "4") (pinfunction "4_4") (pintype "passive"))
      (node (ref "JP16") (pin "5") (pinfunction "5_5") (pintype "passive"))
      (node (ref "JP16") (pin "6") (pinfunction "6_6") (pintype "passive"))
      (node (ref "JP16") (pin "7") (pinfunction "7_7") (pintype "passive"))
      (node (ref "JP16") (pin "8") (pinfunction "8_8") (pintype "passive"))
      (node (ref "JP16") (pin "9") (pinfunction "9_9") (pintype "passive"))
      (node (ref "JP19") (pin "1") (pinfunction "1_1") (pintype "passive"))
      (node (ref "JP19") (pin "10") (pinfunction "10_10") (pintype "passive"))
      (node (ref "JP19") (pin "2") (pinfunction "2_2") (pintype "passive"))
      (node (ref "JP19") (pin "3") (pinfunction "3_3") (pintype "passive"))
      (node (ref "JP19") (pin "4") (pinfunction "4_4") (pintype "passive"))
      (node (ref "JP19") (pin "5") (pinfunction "5_5") (pintype "passive"))
      (node (ref "JP19") (pin "6") (pinfunction "6_6") (pintype "passive"))
      (node (ref "JP19") (pin "7") (pinfunction "7_7") (pintype "passive"))
      (node (ref "JP19") (pin "8") (pinfunction "8_8") (pintype "passive"))
      (node (ref "JP19") (pin "9") (pinfunction "9_9") (pintype "passive"))
    )
    (net (code "93") (name "Net-(LED1-PadC)") (class "Default")
      (node (ref "LED1") (pin "C") (pinfunction "C_C") (pintype "passive"))
      (node (ref "R13") (pin "2") (pinfunction "2_2") (pintype "passive"))
    )
    (net (code "94") (name "VCC") (class "Default")
      (node (ref "C5") (pin "1") (pinfunction "1_1") (pintype "passive"))
      (node (ref "C8") (pin "1") (pinfunction "1_1") (pintype "passive"))
      (node (ref "IC6") (pin "1") (pinfunction "IN_1") (pintype "input"))
      (node (ref "IC8") (pin "1") (pinfunction "IN_1") (pintype "input"))
      (node (ref "POWER") (pin "1") (pinfunction "KL_1") (pintype "passive"))
      (node (ref "SRV1-PWR") (pin "1") (pinfunction "1_1") (pintype "passive"))
    )
    (net (code "95") (name "unconnected-(IC3-OSC1{slash}CLKIN-Pad9)") (class "Default")
      (node (ref "IC3") (pin "9") (pinfunction "OSC1/CLKIN_9") (pintype "input"))
    )
    (net (code "96") (name "unconnected-(IC3-OSC2{slash}CLKOUT-Pad10)") (class "Default")
      (node (ref "IC3") (pin "10") (pinfunction "OSC2/CLKOUT_10") (pintype "output"))
    )
    (net (code "97") (name "unconnected-(IC4-ALERT-Pad17)") (class "Default")
      (node (ref "IC4") (pin "17") (pinfunction "ALERT_17") (pintype "output"))
    )
    (net (code "98") (name "unconnected-(IC5-ADJ-Pad5)") (class "Default")
      (node (ref "IC5") (pin "5") (pinfunction "ADJ_5") (pintype "input"))
    )
    (net (code "99") (name "unconnected-(SD-DAT1|---Pad8)") (class "Default")
      (node (ref "SD") (pin "8") (pinfunction "DAT1|--_8") (pintype "bidirectional"))
    )
    (net (code "100") (name "unconnected-(SD-DAT2|---Pad9)") (class "Default")
      (node (ref "SD") (pin "9") (pinfunction "DAT2|--_9") (pintype "bidirectional"))
    )
  )
)
